# LoRa_RFID_Velvet_Controller.net
KiCad netlist of a schematic drawn in Altium Designer
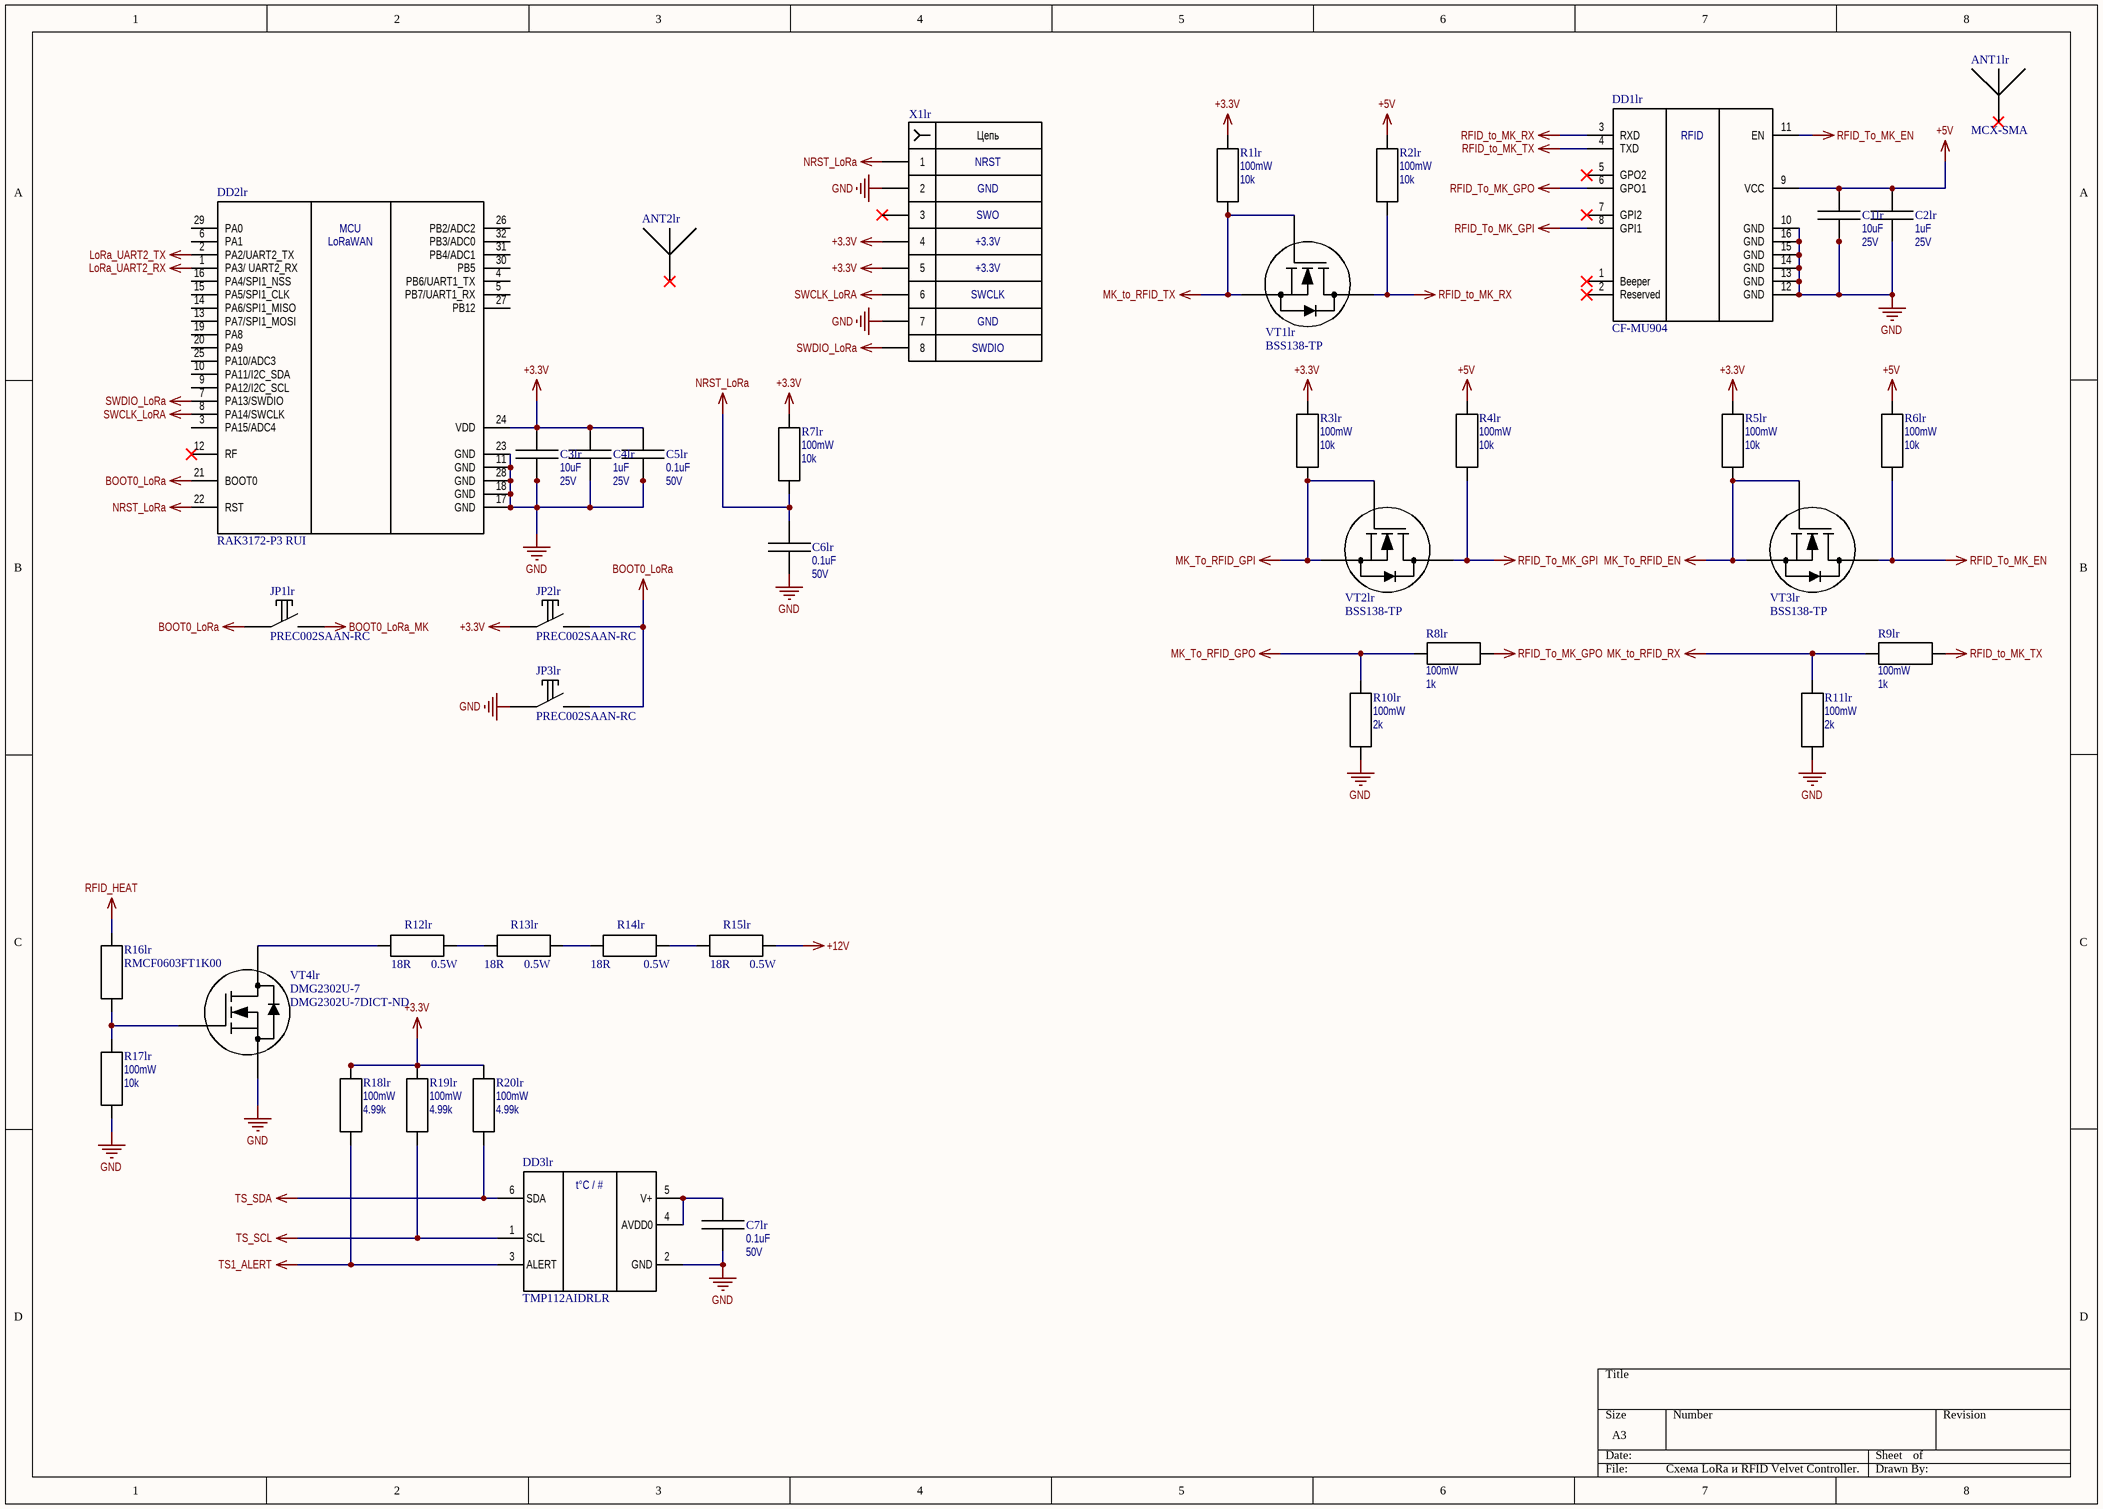
[diagram p0: Схема LoRa и RFID Velvet Controller.SchDoc]

(export (version "E")
  (design (tool "Eeschema 10.0.6"))
  (components
    (comp (ref "ANT1lr")
      (value "MCX-SMA")
      (description "MCX-Male to SMA RF 15cm connector")
      (libsource (lib "Connectors") (part "MCX-SMA"))
    )
    (comp (ref "ANT2lr")
      (value "CA-DKCA0-152L0-AJI0-O")
      (description "WATERPROOF SMA TO IPEX FOR 1.13")
      (libsource (lib "Connectors") (part "CA-DKCA0-152L0-AJI0-O"))
    )
    (comp (ref "C1lr")
      (value "CL31B106KAHNNNE")
      (footprint "CAP 1206 IPC MAX")
      (description "CAP SMD CER 10UF 25V X7R 1206")
      (fields
        (field (name "TOLERANCE") "10%")
        (field (name "CAPACITANCE") "10uF")
        (field (name "RATED VOLTAGE") "25V")
      )
      (libsource (lib "Passive components") (part "CL31B106KAHNNNE"))
    )
    (comp (ref "C2lr")
      (value "TMK107BJ105KA-T")
      (footprint "CAP 0603 IPC MAX")
      (description "CAP SMD CER 1UF 25V X5R 0603")
      (fields
        (field (name "TOLERANCE") "10%")
        (field (name "CAPACITANCE") "1uF")
        (field (name "RATED VOLTAGE") "25V")
      )
      (libsource (lib "Passive components") (part "TMK107BJ105KA-T"))
    )
    (comp (ref "C3lr")
      (value "CL31B106KAHNNNE")
      (footprint "CAP 1206 IPC MAX")
      (description "CAP SMD CER 10UF 25V X7R 1206")
      (fields
        (field (name "TOLERANCE") "10%")
        (field (name "CAPACITANCE") "10uF")
        (field (name "RATED VOLTAGE") "25V")
      )
      (libsource (lib "Passive components") (part "CL31B106KAHNNNE"))
    )
    (comp (ref "C4lr")
      (value "TMK107BJ105KA-T")
      (footprint "CAP 0603 IPC MAX")
      (description "CAP SMD CER 1UF 25V X5R 0603")
      (fields
        (field (name "TOLERANCE") "10%")
        (field (name "CAPACITANCE") "1uF")
        (field (name "RATED VOLTAGE") "25V")
      )
      (libsource (lib "Passive components") (part "TMK107BJ105KA-T"))
    )
    (comp (ref "C5lr")
      (value "GCM188R71H104KA57D")
      (footprint "CAP 0603 IPC MAX")
      (description "CAP SMD CER 0.1UF 50V X7R 0603")
      (fields
        (field (name "TOLERANCE") "10%")
        (field (name "CAPACITANCE") "0.1uF")
        (field (name "RATED VOLTAGE") "50V")
      )
      (libsource (lib "Passive components") (part "GCM188R71H104KA57D"))
    )
    (comp (ref "C6lr")
      (value "GCM188R71H104KA57D")
      (footprint "CAP 0603 IPC MAX")
      (description "CAP SMD CER 0.1UF 50V X7R 0603")
      (fields
        (field (name "TOLERANCE") "10%")
        (field (name "CAPACITANCE") "0.1uF")
        (field (name "RATED VOLTAGE") "50V")
      )
      (libsource (lib "Passive components") (part "GCM188R71H104KA57D"))
    )
    (comp (ref "C7lr")
      (value "GCM188R71H104KA57D")
      (footprint "CAP 0603 IPC MAX")
      (description "CAP SMD CER 0.1UF 50V X7R 0603")
      (fields
        (field (name "TOLERANCE") "10%")
        (field (name "CAPACITANCE") "0.1uF")
        (field (name "RATED VOLTAGE") "50V")
      )
      (libsource (lib "Passive components") (part "GCM188R71H104KA57D"))
    )
    (comp (ref "DD1lr")
      (value "CF-MU904")
      (footprint "CF-MU904")
      (description "UHF RFID Reader Module")
      (libsource (lib "Digital") (part "CF-MU904"))
    )
    (comp (ref "DD2lr")
      (value "RAK3172-P3 RUI")
      (footprint "RAK3172")
      (description "MODULE FOR LORAWAN RAK3172")
      (libsource (lib "Digital") (part "RAK3172-P3 RUI"))
    )
    (comp (ref "DD3lr")
      (value "TMP112AIDRLR")
      (footprint "SOT-563")
      (description "SOT-563 TEMPERATURE SENSORS ROHS")
      (libsource (lib "Digital") (part "TMP112AIDRLR"))
    )
    (comp (ref "JP1lr")
      (value "PREC002SAAN-RC")
      (footprint "2P TH 2.54mm")
      (description "CONN HEADER VERT 2POS 2.54MM")
      (libsource (lib "Connectors") (part "PREC002SAAN-RC"))
    )
    (comp (ref "JP2lr")
      (value "PREC002SAAN-RC")
      (footprint "2P TH 2.54mm")
      (description "CONN HEADER VERT 2POS 2.54MM")
      (libsource (lib "Connectors") (part "PREC002SAAN-RC"))
    )
    (comp (ref "JP3lr")
      (value "PREC002SAAN-RC")
      (footprint "2P TH 2.54mm")
      (description "CONN HEADER VERT 2POS 2.54MM")
      (libsource (lib "Connectors") (part "PREC002SAAN-RC"))
    )
    (comp (ref "R1lr")
      (value "RMCF0603JT10K0")
      (footprint "RES 0603 IPC MAX")
      (description "RES SMD 10K OHM 5% 1/10W 0603")
      (fields
        (field (name "TOLERANCE") "5%")
        (field (name "POWER RATED") "100mW")
        (field (name "RESISTANCE") "10k")
      )
      (libsource (lib "Passive components") (part "RMCF0603JT10K0"))
    )
    (comp (ref "R2lr")
      (value "RMCF0603JT10K0")
      (footprint "RES 0603 IPC MAX")
      (description "RES SMD 10K OHM 5% 1/10W 0603")
      (fields
        (field (name "TOLERANCE") "5%")
        (field (name "POWER RATED") "100mW")
        (field (name "RESISTANCE") "10k")
      )
      (libsource (lib "Passive components") (part "RMCF0603JT10K0"))
    )
    (comp (ref "R3lr")
      (value "RMCF0603JT10K0")
      (footprint "RES 0603 IPC MAX")
      (description "RES SMD 10K OHM 5% 1/10W 0603")
      (fields
        (field (name "TOLERANCE") "5%")
        (field (name "POWER RATED") "100mW")
        (field (name "RESISTANCE") "10k")
      )
      (libsource (lib "Passive components") (part "RMCF0603JT10K0"))
    )
    (comp (ref "R4lr")
      (value "RMCF0603JT10K0")
      (footprint "RES 0603 IPC MAX")
      (description "RES SMD 10K OHM 5% 1/10W 0603")
      (fields
        (field (name "TOLERANCE") "5%")
        (field (name "POWER RATED") "100mW")
        (field (name "RESISTANCE") "10k")
      )
      (libsource (lib "Passive components") (part "RMCF0603JT10K0"))
    )
    (comp (ref "R5lr")
      (value "RMCF0603JT10K0")
      (footprint "RES 0603 IPC MAX")
      (description "RES SMD 10K OHM 5% 1/10W 0603")
      (fields
        (field (name "TOLERANCE") "5%")
        (field (name "POWER RATED") "100mW")
        (field (name "RESISTANCE") "10k")
      )
      (libsource (lib "Passive components") (part "RMCF0603JT10K0"))
    )
    (comp (ref "R6lr")
      (value "RMCF0603JT10K0")
      (footprint "RES 0603 IPC MAX")
      (description "RES SMD 10K OHM 5% 1/10W 0603")
      (fields
        (field (name "TOLERANCE") "5%")
        (field (name "POWER RATED") "100mW")
        (field (name "RESISTANCE") "10k")
      )
      (libsource (lib "Passive components") (part "RMCF0603JT10K0"))
    )
    (comp (ref "R7lr")
      (value "RMCF0603JT10K0")
      (footprint "RES 0603 IPC MAX")
      (description "RES SMD 10K OHM 5% 1/10W 0603")
      (fields
        (field (name "TOLERANCE") "5%")
        (field (name "POWER RATED") "100mW")
        (field (name "RESISTANCE") "10k")
      )
      (libsource (lib "Passive components") (part "RMCF0603JT10K0"))
    )
    (comp (ref "R8lr")
      (value "RMCF0603FT1K00")
      (footprint "RES 0603 IPC MAX")
      (description "RES SMD 1K OHM 1% 1/10W 0603")
      (fields
        (field (name "TOLERANCE") "1%")
        (field (name "RATED POWER") "100mW")
        (field (name "RESISTANCE") "1k")
      )
      (libsource (lib "Passive components") (part "RMCF0603FT1K00"))
    )
    (comp (ref "R9lr")
      (value "RMCF0603FT1K00")
      (footprint "RES 0603 IPC MAX")
      (description "RES SMD 1K OHM 1% 1/10W 0603")
      (fields
        (field (name "TOLERANCE") "1%")
        (field (name "RATED POWER") "100mW")
        (field (name "RESISTANCE") "1k")
      )
      (libsource (lib "Passive components") (part "RMCF0603FT1K00"))
    )
    (comp (ref "R10lr")
      (value "RMCF0603FT2K00")
      (footprint "RES 0603 IPC MAX")
      (description "RES SMD 2K OHM 1% 1/10W 0603")
      (fields
        (field (name "TOLERANCE") "1%")
        (field (name "RATED POWER") "100mW")
        (field (name "RESISTANCE") "2k")
      )
      (libsource (lib "Passive components") (part "RMCF0603FT2K00"))
    )
    (comp (ref "R11lr")
      (value "RMCF0603FT2K00")
      (footprint "RES 0603 IPC MAX")
      (description "RES SMD 2K OHM 1% 1/10W 0603")
      (fields
        (field (name "TOLERANCE") "1%")
        (field (name "RATED POWER") "100mW")
        (field (name "RESISTANCE") "2k")
      )
      (libsource (lib "Passive components") (part "RMCF0603FT2K00"))
    )
    (comp (ref "R12lr")
      (value "RMCF1210JT18R0")
      (footprint "RES 1210")
      (description "RES SMD 18 OHM 5% 1/2W 1210")
      (fields
        (field (name "RESISTANCE") "18R")
        (field (name "TOLERANCE") "5%")
        (field (name "RATED POWER") "0.5W")
      )
      (libsource (lib "Passive components") (part "RMCF1210JT18R0"))
    )
    (comp (ref "R13lr")
      (value "RMCF1210JT18R0")
      (footprint "RES 1210")
      (description "RES SMD 18 OHM 5% 1/2W 1210")
      (fields
        (field (name "RESISTANCE") "18R")
        (field (name "TOLERANCE") "5%")
        (field (name "RATED POWER") "0.5W")
      )
      (libsource (lib "Passive components") (part "RMCF1210JT18R0"))
    )
    (comp (ref "R14lr")
      (value "RMCF1210JT18R0")
      (footprint "RES 1210")
      (description "RES SMD 18 OHM 5% 1/2W 1210")
      (fields
        (field (name "RESISTANCE") "18R")
        (field (name "TOLERANCE") "5%")
        (field (name "RATED POWER") "0.5W")
      )
      (libsource (lib "Passive components") (part "RMCF1210JT18R0"))
    )
    (comp (ref "R15lr")
      (value "RMCF1210JT18R0")
      (footprint "RES 1210")
      (description "RES SMD 18 OHM 5% 1/2W 1210")
      (fields
        (field (name "RESISTANCE") "18R")
        (field (name "TOLERANCE") "5%")
        (field (name "RATED POWER") "0.5W")
      )
      (libsource (lib "Passive components") (part "RMCF1210JT18R0"))
    )
    (comp (ref "R16lr")
      (value "RMCF0603FT1K00")
      (footprint "RES 0603 IPC MAX")
      (description "RES SMD 1K OHM 1% 1/10W 0603")
      (fields (field (name "TOLERANCE") "1%"))
      (libsource (lib "Passive components") (part "RMCF0603FT1K00"))
    )
    (comp (ref "R17lr")
      (value "RMCF0603JT10K0")
      (footprint "RES 0603 IPC MAX")
      (description "RES SMD 10K OHM 5% 1/10W 0603")
      (fields
        (field (name "TOLERANCE") "5%")
        (field (name "POWER RATED") "100mW")
        (field (name "RESISTANCE") "10k")
      )
      (libsource (lib "Passive components") (part "RMCF0603JT10K0"))
    )
    (comp (ref "R18lr")
      (value "RC0603FR-074K99L")
      (footprint "RES 0603 IPC MAX")
      (description "RES SMD 4.99K OHM 1% 1/10W 0603")
      (fields
        (field (name "TOLERANCE") "1%")
        (field (name "RATED POWER") "100mW")
        (field (name "RESISTANCE") "4.99k")
      )
      (libsource (lib "Passive components") (part "RC0603FR-074K99L"))
    )
    (comp (ref "R19lr")
      (value "RC0603FR-074K99L")
      (footprint "RES 0603 IPC MAX")
      (description "RES SMD 4.99K OHM 1% 1/10W 0603")
      (fields
        (field (name "TOLERANCE") "1%")
        (field (name "RATED POWER") "100mW")
        (field (name "RESISTANCE") "4.99k")
      )
      (libsource (lib "Passive components") (part "RC0603FR-074K99L"))
    )
    (comp (ref "R20lr")
      (value "RC0603FR-074K99L")
      (footprint "RES 0603 IPC MAX")
      (description "RES SMD 4.99K OHM 1% 1/10W 0603")
      (fields
        (field (name "TOLERANCE") "1%")
        (field (name "RATED POWER") "100mW")
        (field (name "RESISTANCE") "4.99k")
      )
      (libsource (lib "Passive components") (part "RC0603FR-074K99L"))
    )
    (comp (ref "VT1lr")
      (value "BSS138-TP")
      (footprint "SOT-23-3")
      (description "MOSFET N-CH 50V 220MA SOT23")
      (libsource (lib "MOSFET") (part "BSS138-TP"))
    )
    (comp (ref "VT2lr")
      (value "BSS138-TP")
      (footprint "SOT-23-3")
      (description "MOSFET N-CH 50V 220MA SOT23")
      (libsource (lib "MOSFET") (part "BSS138-TP"))
    )
    (comp (ref "VT3lr")
      (value "BSS138-TP")
      (footprint "SOT-23-3")
      (description "MOSFET N-CH 50V 220MA SOT23")
      (libsource (lib "MOSFET") (part "BSS138-TP"))
    )
    (comp (ref "VT4lr")
      (value "DMG2302U-7")
      (footprint "SOT-23-3")
      (description "MOSFET N-CH 20V 4.2A SOT23-3")
      (fields (field (name "SUPPLIER PART NUMBER 1") "DMG2302U-7DICT-ND"))
      (libsource (lib "MOSFET") (part "DMG2302U-7"))
    )
    (comp (ref "X1lr")
      (value "TSW-104-07-F-D")
      (footprint "HEADER 2.54mm 2ROW 8PIN")
      (description "CONN HEADER VERT 8POS 2.54MM 2ROWx4")
      (libsource (lib "Connectors") (part "TSW-104-07-F-D"))
    )
  )
  (nets
    (net (code "1") (name "+3.3V") (class "Default")
      (node (ref "C3lr") (pin "1") (pinfunction "1_1") (pintype "passive"))
      (node (ref "C4lr") (pin "1") (pinfunction "1_1") (pintype "passive"))
      (node (ref "C5lr") (pin "1") (pinfunction "1_1") (pintype "passive"))
      (node (ref "DD2lr") (pin "24") (pinfunction "VDD_24") (pintype "passive"))
      (node (ref "JP2lr") (pin "1") (pinfunction "1_1") (pintype "passive"))
      (node (ref "R18lr") (pin "2") (pinfunction "2_2") (pintype "passive"))
      (node (ref "R19lr") (pin "2") (pinfunction "2_2") (pintype "passive"))
      (node (ref "R1lr") (pin "2") (pinfunction "2_2") (pintype "passive"))
      (node (ref "R20lr") (pin "2") (pinfunction "2_2") (pintype "passive"))
      (node (ref "R3lr") (pin "2") (pinfunction "2_2") (pintype "passive"))
      (node (ref "R5lr") (pin "2") (pinfunction "2_2") (pintype "passive"))
      (node (ref "R7lr") (pin "2") (pinfunction "2_2") (pintype "passive"))
      (node (ref "X1lr") (pin "4") (pinfunction "4_4") (pintype "passive"))
      (node (ref "X1lr") (pin "5") (pinfunction "5_5") (pintype "passive"))
    )
    (net (code "2") (name "+5V") (class "Default")
      (node (ref "C1lr") (pin "1") (pinfunction "1_1") (pintype "passive"))
      (node (ref "C2lr") (pin "1") (pinfunction "1_1") (pintype "passive"))
      (node (ref "DD1lr") (pin "9") (pinfunction "VCC_9") (pintype "passive"))
      (node (ref "R2lr") (pin "2") (pinfunction "2_2") (pintype "passive"))
      (node (ref "R4lr") (pin "2") (pinfunction "2_2") (pintype "passive"))
      (node (ref "R6lr") (pin "2") (pinfunction "2_2") (pintype "passive"))
    )
    (net (code "3") (name "+12V") (class "Default")
      (node (ref "R15lr") (pin "2") (pinfunction "2_2") (pintype "passive"))
    )
    (net (code "4") (name "BOOT0_LoRa") (class "Default")
      (node (ref "DD2lr") (pin "21") (pinfunction "BOOT0_21") (pintype "passive"))
      (node (ref "JP1lr") (pin "1") (pinfunction "1_1") (pintype "passive"))
      (node (ref "JP2lr") (pin "2") (pinfunction "2_2") (pintype "passive"))
      (node (ref "JP3lr") (pin "2") (pinfunction "2_2") (pintype "passive"))
    )
    (net (code "5") (name "BOOT0_LoRa_MK") (class "Default")
      (node (ref "JP1lr") (pin "2") (pinfunction "2_2") (pintype "passive"))
    )
    (net (code "6") (name "GND") (class "Default")
      (node (ref "C1lr") (pin "2") (pinfunction "2_2") (pintype "passive"))
      (node (ref "C2lr") (pin "2") (pinfunction "2_2") (pintype "passive"))
      (node (ref "C3lr") (pin "2") (pinfunction "2_2") (pintype "passive"))
      (node (ref "C4lr") (pin "2") (pinfunction "2_2") (pintype "passive"))
      (node (ref "C5lr") (pin "2") (pinfunction "2_2") (pintype "passive"))
      (node (ref "C6lr") (pin "2") (pinfunction "2_2") (pintype "passive"))
      (node (ref "C7lr") (pin "2") (pinfunction "2_2") (pintype "passive"))
      (node (ref "DD1lr") (pin "10") (pinfunction "GND_10") (pintype "passive"))
      (node (ref "DD1lr") (pin "12") (pinfunction "GND_12") (pintype "passive"))
      (node (ref "DD1lr") (pin "13") (pinfunction "GND_13") (pintype "passive"))
      (node (ref "DD1lr") (pin "14") (pinfunction "GND_14") (pintype "passive"))
      (node (ref "DD1lr") (pin "15") (pinfunction "GND_15") (pintype "passive"))
      (node (ref "DD1lr") (pin "16") (pinfunction "GND_16") (pintype "passive"))
      (node (ref "DD2lr") (pin "11") (pinfunction "GND_11") (pintype "passive"))
      (node (ref "DD2lr") (pin "17") (pinfunction "GND_17") (pintype "passive"))
      (node (ref "DD2lr") (pin "18") (pinfunction "GND_18") (pintype "passive"))
      (node (ref "DD2lr") (pin "23") (pinfunction "GND_23") (pintype "passive"))
      (node (ref "DD2lr") (pin "28") (pinfunction "GND_28") (pintype "passive"))
      (node (ref "DD3lr") (pin "2") (pinfunction "GND_2") (pintype "passive"))
      (node (ref "JP3lr") (pin "1") (pinfunction "1_1") (pintype "passive"))
      (node (ref "R10lr") (pin "1") (pinfunction "1_1") (pintype "passive"))
      (node (ref "R11lr") (pin "1") (pinfunction "1_1") (pintype "passive"))
      (node (ref "R17lr") (pin "1") (pinfunction "1_1") (pintype "passive"))
      (node (ref "VT4lr") (pin "2") (pinfunction "S_2") (pintype "passive"))
      (node (ref "X1lr") (pin "2") (pinfunction "2_2") (pintype "passive"))
      (node (ref "X1lr") (pin "7") (pinfunction "7_7") (pintype "passive"))
    )
    (net (code "7") (name "LoRa_UART2_RX") (class "Default")
      (node (ref "DD2lr") (pin "1") (pinfunction "PA3/_UART2_RX_1") (pintype "passive"))
    )
    (net (code "8") (name "LoRa_UART2_TX") (class "Default")
      (node (ref "DD2lr") (pin "2") (pinfunction "PA2/UART2_TX_2") (pintype "passive"))
    )
    (net (code "9") (name "MK_To_RFID_EN") (class "Default")
      (node (ref "R5lr") (pin "1") (pinfunction "1_1") (pintype "passive"))
      (node (ref "VT3lr") (pin "1") (pinfunction "G_1") (pintype "passive"))
      (node (ref "VT3lr") (pin "2") (pinfunction "S_2") (pintype "passive"))
    )
    (net (code "10") (name "MK_To_RFID_GPI") (class "Default")
      (node (ref "R3lr") (pin "1") (pinfunction "1_1") (pintype "passive"))
      (node (ref "VT2lr") (pin "1") (pinfunction "G_1") (pintype "passive"))
      (node (ref "VT2lr") (pin "2") (pinfunction "S_2") (pintype "passive"))
    )
    (net (code "11") (name "MK_To_RFID_GPO") (class "Default")
      (node (ref "R10lr") (pin "2") (pinfunction "2_2") (pintype "passive"))
      (node (ref "R8lr") (pin "1") (pinfunction "1_1") (pintype "passive"))
    )
    (net (code "12") (name "MK_to_RFID_RX") (class "Default")
      (node (ref "R11lr") (pin "2") (pinfunction "2_2") (pintype "passive"))
      (node (ref "R9lr") (pin "1") (pinfunction "1_1") (pintype "passive"))
    )
    (net (code "13") (name "MK_to_RFID_TX") (class "Default")
      (node (ref "R1lr") (pin "1") (pinfunction "1_1") (pintype "passive"))
      (node (ref "VT1lr") (pin "1") (pinfunction "G_1") (pintype "passive"))
      (node (ref "VT1lr") (pin "2") (pinfunction "S_2") (pintype "passive"))
    )
    (net (code "14") (name "NRST_LoRa") (class "Default")
      (node (ref "C6lr") (pin "1") (pinfunction "1_1") (pintype "passive"))
      (node (ref "DD2lr") (pin "22") (pinfunction "RST_22") (pintype "passive"))
      (node (ref "R7lr") (pin "1") (pinfunction "1_1") (pintype "passive"))
      (node (ref "X1lr") (pin "1") (pinfunction "1_1") (pintype "passive"))
    )
    (net (code "15") (name "Net-(DD3lr-AVDD0)") (class "Default")
      (node (ref "C7lr") (pin "1") (pinfunction "1_1") (pintype "passive"))
      (node (ref "DD3lr") (pin "4") (pinfunction "AVDD0_4") (pintype "passive"))
      (node (ref "DD3lr") (pin "5") (pinfunction "V+_5") (pintype "passive"))
    )
    (net (code "16") (name "Net-(R12lr-Pad2)") (class "Default")
      (node (ref "R12lr") (pin "2") (pinfunction "2_2") (pintype "passive"))
      (node (ref "R13lr") (pin "1") (pinfunction "1_1") (pintype "passive"))
    )
    (net (code "17") (name "Net-(R13lr-Pad2)") (class "Default")
      (node (ref "R13lr") (pin "2") (pinfunction "2_2") (pintype "passive"))
      (node (ref "R14lr") (pin "1") (pinfunction "1_1") (pintype "passive"))
    )
    (net (code "18") (name "Net-(R14lr-Pad2)") (class "Default")
      (node (ref "R14lr") (pin "2") (pinfunction "2_2") (pintype "passive"))
      (node (ref "R15lr") (pin "1") (pinfunction "1_1") (pintype "passive"))
    )
    (net (code "19") (name "Net-(VT4lr-D)") (class "Default")
      (node (ref "R12lr") (pin "1") (pinfunction "1_1") (pintype "passive"))
      (node (ref "VT4lr") (pin "3") (pinfunction "D_3") (pintype "passive"))
    )
    (net (code "20") (name "Net-(VT4lr-G)") (class "Default")
      (node (ref "R16lr") (pin "1") (pinfunction "1_1") (pintype "passive"))
      (node (ref "R17lr") (pin "2") (pinfunction "2_2") (pintype "passive"))
      (node (ref "VT4lr") (pin "1") (pinfunction "G_1") (pintype "passive"))
    )
    (net (code "21") (name "RFID_HEAT") (class "Default")
      (node (ref "R16lr") (pin "2") (pinfunction "2_2") (pintype "passive"))
    )
    (net (code "22") (name "RFID_To_MK_EN") (class "Default")
      (node (ref "DD1lr") (pin "11") (pinfunction "EN_11") (pintype "passive"))
      (node (ref "R6lr") (pin "1") (pinfunction "1_1") (pintype "passive"))
      (node (ref "VT3lr") (pin "3") (pinfunction "D_3") (pintype "passive"))
    )
    (net (code "23") (name "RFID_To_MK_GPI") (class "Default")
      (node (ref "DD1lr") (pin "8") (pinfunction "GPI1_8") (pintype "passive"))
      (node (ref "R4lr") (pin "1") (pinfunction "1_1") (pintype "passive"))
      (node (ref "VT2lr") (pin "3") (pinfunction "D_3") (pintype "passive"))
    )
    (net (code "24") (name "RFID_To_MK_GPO") (class "Default")
      (node (ref "DD1lr") (pin "6") (pinfunction "GPO1_6") (pintype "passive"))
      (node (ref "R8lr") (pin "2") (pinfunction "2_2") (pintype "passive"))
    )
    (net (code "25") (name "RFID_to_MK_RX") (class "Default")
      (node (ref "DD1lr") (pin "3") (pinfunction "RXD_3") (pintype "passive"))
      (node (ref "R2lr") (pin "1") (pinfunction "1_1") (pintype "passive"))
      (node (ref "VT1lr") (pin "3") (pinfunction "D_3") (pintype "passive"))
    )
    (net (code "26") (name "RFID_to_MK_TX") (class "Default")
      (node (ref "DD1lr") (pin "4") (pinfunction "TXD_4") (pintype "passive"))
      (node (ref "R9lr") (pin "2") (pinfunction "2_2") (pintype "passive"))
    )
    (net (code "27") (name "SWCLK_LoRA") (class "Default")
      (node (ref "DD2lr") (pin "8") (pinfunction "PA14/SWCLK_8") (pintype "passive"))
      (node (ref "X1lr") (pin "6") (pinfunction "6_6") (pintype "passive"))
    )
    (net (code "28") (name "SWDIO_LoRa") (class "Default")
      (node (ref "DD2lr") (pin "7") (pinfunction "PA13/SWDIO_7") (pintype "passive"))
      (node (ref "X1lr") (pin "8") (pinfunction "8_8") (pintype "passive"))
    )
    (net (code "29") (name "TS1_ALERT") (class "Default")
      (node (ref "DD3lr") (pin "3") (pinfunction "ALERT_3") (pintype "passive"))
      (node (ref "R18lr") (pin "1") (pinfunction "1_1") (pintype "passive"))
    )
    (net (code "30") (name "TS_SCL") (class "Default")
      (node (ref "DD3lr") (pin "1") (pinfunction "SCL_1") (pintype "passive"))
      (node (ref "R19lr") (pin "1") (pinfunction "1_1") (pintype "passive"))
    )
    (net (code "31") (name "TS_SDA") (class "Default")
      (node (ref "DD3lr") (pin "6") (pinfunction "SDA_6") (pintype "passive"))
      (node (ref "R20lr") (pin "1") (pinfunction "1_1") (pintype "passive"))
    )
    (net (code "32") (name "unconnected-(ANT1lr-Pad1)") (class "Default")
      (node (ref "ANT1lr") (pin "1") (pinfunction "1_1") (pintype "passive+no_connect"))
    )
    (net (code "33") (name "unconnected-(ANT2lr-Pad1)") (class "Default")
      (node (ref "ANT2lr") (pin "1") (pinfunction "1_1") (pintype "passive+no_connect"))
    )
    (net (code "34") (name "unconnected-(DD1lr-Beeper-Pad1)") (class "Default")
      (node (ref "DD1lr") (pin "1") (pinfunction "Beeper_1") (pintype "passive+no_connect"))
    )
    (net (code "35") (name "unconnected-(DD1lr-GPI2-Pad7)") (class "Default")
      (node (ref "DD1lr") (pin "7") (pinfunction "GPI2_7") (pintype "passive+no_connect"))
    )
    (net (code "36") (name "unconnected-(DD1lr-GPO2-Pad5)") (class "Default")
      (node (ref "DD1lr") (pin "5") (pinfunction "GPO2_5") (pintype "passive+no_connect"))
    )
    (net (code "37") (name "unconnected-(DD1lr-Reserved-Pad2)") (class "Default")
      (node (ref "DD1lr") (pin "2") (pinfunction "Reserved_2") (pintype "passive+no_connect"))
    )
    (net (code "38") (name "unconnected-(DD2lr-PA0-Pad29)") (class "Default")
      (node (ref "DD2lr") (pin "29") (pinfunction "PA0_29") (pintype "passive"))
    )
    (net (code "39") (name "unconnected-(DD2lr-PA1-Pad6)") (class "Default")
      (node (ref "DD2lr") (pin "6") (pinfunction "PA1_6") (pintype "passive"))
    )
    (net (code "40") (name "unconnected-(DD2lr-PA4{slash}SPI1_NSS-Pad16)") (class "Default")
      (node (ref "DD2lr") (pin "16") (pinfunction "PA4/SPI1_NSS_16") (pintype "passive"))
    )
    (net (code "41") (name "unconnected-(DD2lr-PA5{slash}SPI1_CLK-Pad15)") (class "Default")
      (node (ref "DD2lr") (pin "15") (pinfunction "PA5/SPI1_CLK_15") (pintype "passive"))
    )
    (net (code "42") (name "unconnected-(DD2lr-PA6{slash}SPI1_MISO-Pad14)") (class "Default")
      (node (ref "DD2lr") (pin "14") (pinfunction "PA6/SPI1_MISO_14") (pintype "passive"))
    )
    (net (code "43") (name "unconnected-(DD2lr-PA7{slash}SPI1_MOSI-Pad13)") (class "Default")
      (node (ref "DD2lr") (pin "13") (pinfunction "PA7/SPI1_MOSI_13") (pintype "passive"))
    )
    (net (code "44") (name "unconnected-(DD2lr-PA8-Pad19)") (class "Default")
      (node (ref "DD2lr") (pin "19") (pinfunction "PA8_19") (pintype "passive"))
    )
    (net (code "45") (name "unconnected-(DD2lr-PA9-Pad20)") (class "Default")
      (node (ref "DD2lr") (pin "20") (pinfunction "PA9_20") (pintype "passive"))
    )
    (net (code "46") (name "unconnected-(DD2lr-PA10{slash}ADC3-Pad25)") (class "Default")
      (node (ref "DD2lr") (pin "25") (pinfunction "PA10/ADC3_25") (pintype "passive"))
    )
    (net (code "47") (name "unconnected-(DD2lr-PA11{slash}I2C_SDA-Pad10)") (class "Default")
      (node (ref "DD2lr") (pin "10") (pinfunction "PA11/I2C_SDA_10") (pintype "passive"))
    )
    (net (code "48") (name "unconnected-(DD2lr-PA12{slash}I2C_SCL-Pad9)") (class "Default")
      (node (ref "DD2lr") (pin "9") (pinfunction "PA12/I2C_SCL_9") (pintype "passive"))
    )
    (net (code "49") (name "unconnected-(DD2lr-PA15{slash}ADC4-Pad3)") (class "Default")
      (node (ref "DD2lr") (pin "3") (pinfunction "PA15/ADC4_3") (pintype "passive"))
    )
    (net (code "50") (name "unconnected-(DD2lr-PB2{slash}ADC2-Pad26)") (class "Default")
      (node (ref "DD2lr") (pin "26") (pinfunction "PB2/ADC2_26") (pintype "passive"))
    )
    (net (code "51") (name "unconnected-(DD2lr-PB3{slash}ADC0-Pad32)") (class "Default")
      (node (ref "DD2lr") (pin "32") (pinfunction "PB3/ADC0_32") (pintype "passive"))
    )
    (net (code "52") (name "unconnected-(DD2lr-PB4{slash}ADC1-Pad31)") (class "Default")
      (node (ref "DD2lr") (pin "31") (pinfunction "PB4/ADC1_31") (pintype "passive"))
    )
    (net (code "53") (name "unconnected-(DD2lr-PB5-Pad30)") (class "Default")
      (node (ref "DD2lr") (pin "30") (pinfunction "PB5_30") (pintype "passive"))
    )
    (net (code "54") (name "unconnected-(DD2lr-PB6{slash}UART1_TX-Pad4)") (class "Default")
      (node (ref "DD2lr") (pin "4") (pinfunction "PB6/UART1_TX_4") (pintype "passive"))
    )
    (net (code "55") (name "unconnected-(DD2lr-PB7{slash}UART1_RX-Pad5)") (class "Default")
      (node (ref "DD2lr") (pin "5") (pinfunction "PB7/UART1_RX_5") (pintype "passive"))
    )
    (net (code "56") (name "unconnected-(DD2lr-PB12-Pad27)") (class "Default")
      (node (ref "DD2lr") (pin "27") (pinfunction "PB12_27") (pintype "passive"))
    )
    (net (code "57") (name "unconnected-(DD2lr-RF-Pad12)") (class "Default")
      (node (ref "DD2lr") (pin "12") (pinfunction "RF_12") (pintype "passive+no_connect"))
    )
    (net (code "58") (name "unconnected-(X1lr-Pad3)") (class "Default")
      (node (ref "X1lr") (pin "3") (pinfunction "3_3") (pintype "passive+no_connect"))
    )
  )
)
